# DigitalesSCH.net
KiCad netlist of a schematic drawn in EAGLE
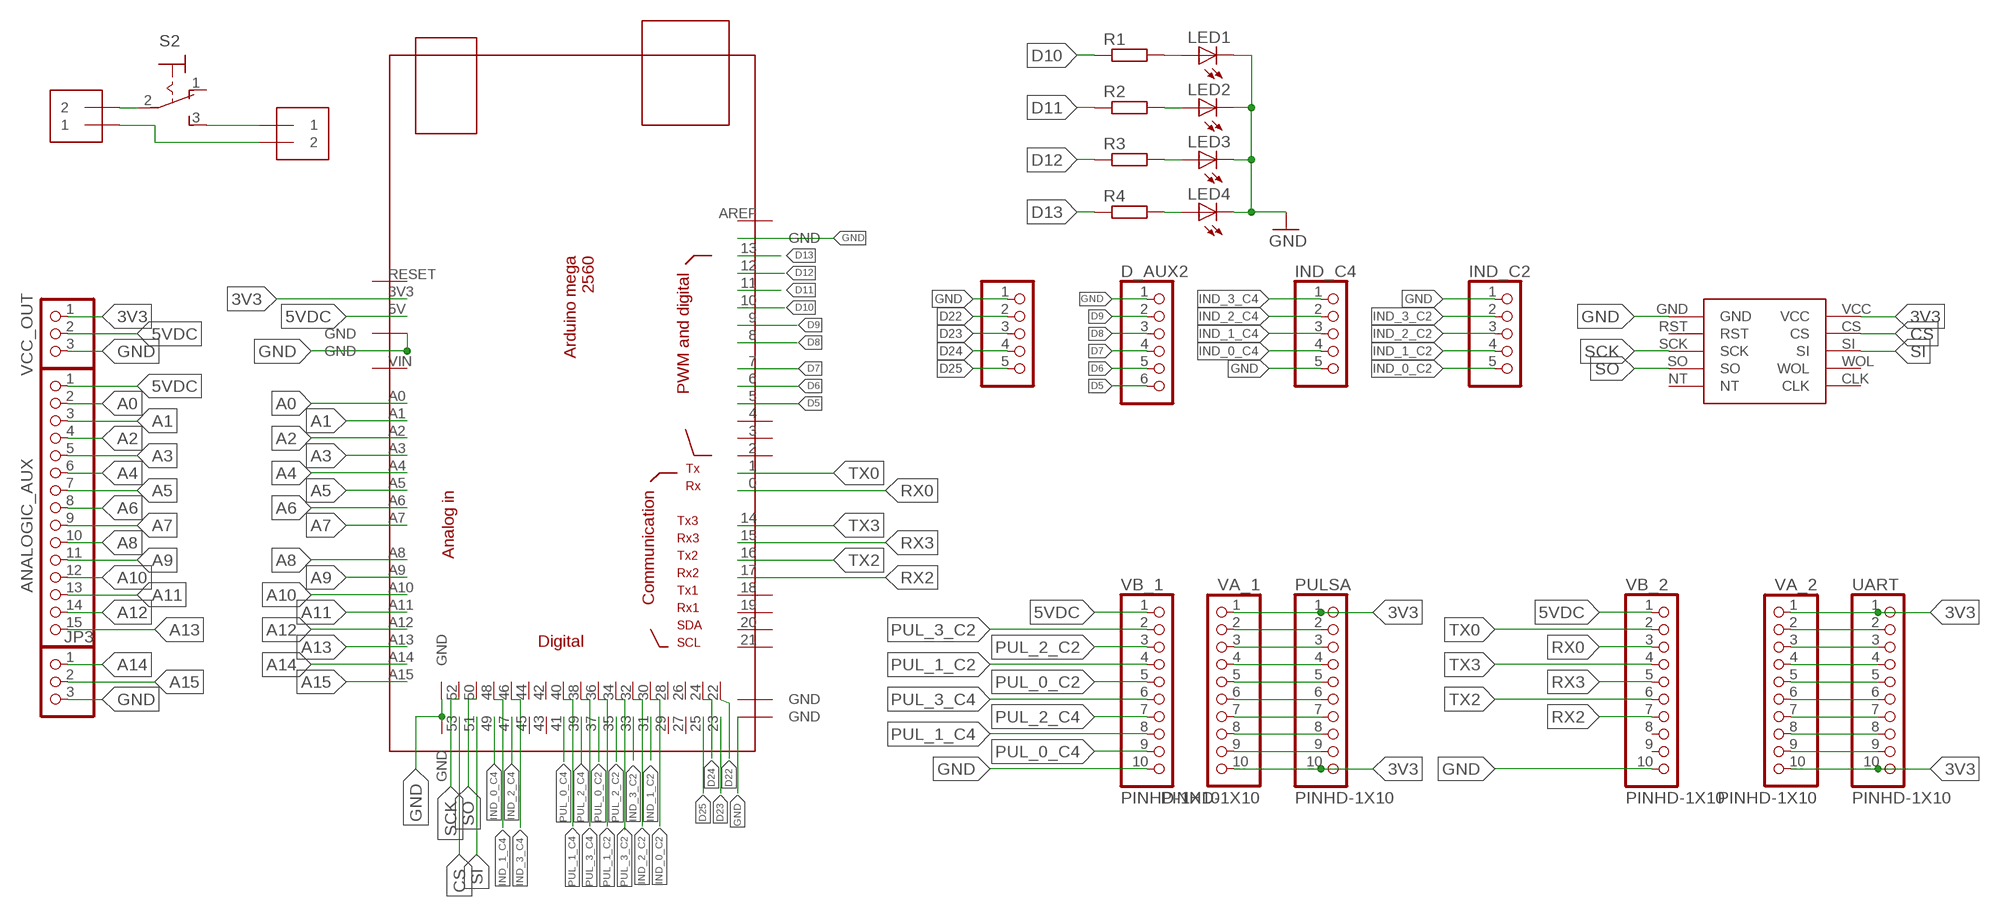
[diagram p0: schematic, sheet 1]

(export (version "E")
  (design (tool "Eeschema 10.0.6"))
  (components
    (comp (ref "ANALOGIC_AUX")
      (value "PINHD-1X15")
      (footprint "eagle-import:1X15")
      (libsource (lib "eagle-import") (part "PINHD-1X15"))
    )
    (comp (ref "D_AUX1")
      (value "PINHD-1X5")
      (footprint "eagle-import:1X05")
      (libsource (lib "eagle-import") (part "PINHD-1X5"))
    )
    (comp (ref "D_AUX2")
      (value "PINHD-1X6")
      (footprint "eagle-import:1X06")
      (libsource (lib "eagle-import") (part "PINHD-1X6"))
    )
    (comp (ref "IND_C2")
      (value "PINHD-1X5")
      (footprint "eagle-import:1X05")
      (libsource (lib "eagle-import") (part "PINHD-1X5"))
    )
    (comp (ref "IND_C4")
      (value "PINHD-1X5")
      (footprint "eagle-import:1X05")
      (libsource (lib "eagle-import") (part "PINHD-1X5"))
    )
    (comp (ref "JP3")
      (value "PINHD-1X3")
      (footprint "eagle-import:1X03")
      (libsource (lib "eagle-import") (part "PINHD-1X3"))
    )
    (comp (ref "LED1")
      (value "LED3MM")
      (footprint "eagle-import:LED3MM")
      (libsource (lib "eagle-import") (part "LED3MM"))
    )
    (comp (ref "LED2")
      (value "LED3MM")
      (footprint "eagle-import:LED3MM")
      (libsource (lib "eagle-import") (part "LED3MM"))
    )
    (comp (ref "LED3")
      (value "LED3MM")
      (footprint "eagle-import:LED3MM")
      (libsource (lib "eagle-import") (part "LED3MM"))
    )
    (comp (ref "LED4")
      (value "LED3MM")
      (footprint "eagle-import:LED3MM")
      (libsource (lib "eagle-import") (part "LED3MM"))
    )
    (comp (ref "PULSA")
      (value "PINHD-1X10")
      (footprint "eagle-import:1X10-BIG")
      (libsource (lib "eagle-import") (part "PINHD-1X10"))
    )
    (comp (ref "R1")
      (value "R-EU_M1206")
      (footprint "eagle-import:M1206")
      (libsource (lib "eagle-import") (part "R-EU_M1206"))
    )
    (comp (ref "R2")
      (value "R-EU_M1206")
      (footprint "eagle-import:M1206")
      (libsource (lib "eagle-import") (part "R-EU_M1206"))
    )
    (comp (ref "R3")
      (value "R-EU_M1206")
      (footprint "eagle-import:M1206")
      (libsource (lib "eagle-import") (part "R-EU_M1206"))
    )
    (comp (ref "R4")
      (value "R-EU_M1206")
      (footprint "eagle-import:M1206")
      (libsource (lib "eagle-import") (part "R-EU_M1206"))
    )
    (comp (ref "S2")
      (value "M9040P")
      (footprint "eagle-import:M9040P")
      (libsource (lib "eagle-import") (part "M9040P"))
    )
    (comp (ref "U$1")
      (value "MEGA_DEVICE")
      (footprint "eagle-import:MEGAOUTLINE")
      (libsource (lib "eagle-import") (part "MEGA_DEVICE"))
    )
    (comp (ref "U$2")
      (value "ENC28J60")
      (footprint "eagle-import:ENC28J60")
      (libsource (lib "eagle-import") (part "ENC28J60"))
    )
    (comp (ref "UART")
      (value "PINHD-1X10")
      (footprint "eagle-import:1X10-BIG")
      (libsource (lib "eagle-import") (part "PINHD-1X10"))
    )
    (comp (ref "VA_1")
      (value "PINHD-1X10")
      (footprint "eagle-import:1X10-BIG")
      (libsource (lib "eagle-import") (part "PINHD-1X10"))
    )
    (comp (ref "VA_2")
      (value "PINHD-1X10")
      (footprint "eagle-import:1X10-BIG")
      (libsource (lib "eagle-import") (part "PINHD-1X10"))
    )
    (comp (ref "VB_1")
      (value "PINHD-1X10")
      (footprint "eagle-import:1X10-BIG")
      (libsource (lib "eagle-import") (part "PINHD-1X10"))
    )
    (comp (ref "VB_2")
      (value "PINHD-1X10")
      (footprint "eagle-import:1X10-BIG")
      (libsource (lib "eagle-import") (part "PINHD-1X10"))
    )
    (comp (ref "VCC_OUT")
      (value "PINHD-1X3")
      (footprint "eagle-import:1X03")
      (libsource (lib "eagle-import") (part "PINHD-1X3"))
    )
    (comp (ref "VIN")
      (value "1X2-3.5MM")
      (footprint "eagle-import:1X2-3.5MM")
      (libsource (lib "eagle-import") (part "1X2-3.5MM"))
    )
    (comp (ref "VOUT")
      (value "1X2-3.5MM")
      (footprint "eagle-import:1X2-3.5MM")
      (libsource (lib "eagle-import") (part "1X2-3.5MM"))
    )
  )
  (nets
    (net (code "1") (name "3V3") (class "Default")
      (node (ref "PULSA") (pin "1") (pinfunction "1_1") (pintype "passive"))
      (node (ref "PULSA") (pin "10") (pinfunction "10_10") (pintype "passive"))
      (node (ref "U$1") (pin "3V3") (pinfunction "3V3_3V3") (pintype "bidirectional"))
      (node (ref "U$2") (pin "VCC") (pinfunction "VCC_VCC") (pintype "bidirectional"))
      (node (ref "UART") (pin "1") (pinfunction "1_1") (pintype "passive"))
      (node (ref "UART") (pin "10") (pinfunction "10_10") (pintype "passive"))
      (node (ref "VA_1") (pin "1") (pinfunction "1_1") (pintype "passive"))
      (node (ref "VA_1") (pin "10") (pinfunction "10_10") (pintype "passive"))
      (node (ref "VA_2") (pin "1") (pinfunction "1_1") (pintype "passive"))
      (node (ref "VA_2") (pin "10") (pinfunction "10_10") (pintype "passive"))
      (node (ref "VCC_OUT") (pin "1") (pinfunction "1_1") (pintype "passive"))
    )
    (net (code "2") (name "5VDC") (class "Default")
      (node (ref "ANALOGIC_AUX") (pin "1") (pinfunction "1_1") (pintype "passive"))
      (node (ref "U$1") (pin "5V") (pinfunction "5V_5V") (pintype "bidirectional"))
      (node (ref "VB_1") (pin "1") (pinfunction "1_1") (pintype "passive"))
      (node (ref "VB_2") (pin "1") (pinfunction "1_1") (pintype "passive"))
      (node (ref "VCC_OUT") (pin "2") (pinfunction "2_2") (pintype "passive"))
    )
    (net (code "3") (name "A0") (class "Default")
      (node (ref "ANALOGIC_AUX") (pin "2") (pinfunction "2_2") (pintype "passive"))
      (node (ref "U$1") (pin "A0") (pinfunction "A0_A0") (pintype "bidirectional"))
    )
    (net (code "4") (name "A1") (class "Default")
      (node (ref "ANALOGIC_AUX") (pin "3") (pinfunction "3_3") (pintype "passive"))
      (node (ref "U$1") (pin "A1") (pinfunction "A1_A1") (pintype "bidirectional"))
    )
    (net (code "5") (name "A2") (class "Default")
      (node (ref "ANALOGIC_AUX") (pin "4") (pinfunction "4_4") (pintype "passive"))
      (node (ref "U$1") (pin "A2") (pinfunction "A2_A2") (pintype "bidirectional"))
    )
    (net (code "6") (name "A3") (class "Default")
      (node (ref "ANALOGIC_AUX") (pin "5") (pinfunction "5_5") (pintype "passive"))
      (node (ref "U$1") (pin "A3") (pinfunction "A3_A3") (pintype "bidirectional"))
    )
    (net (code "7") (name "A4") (class "Default")
      (node (ref "ANALOGIC_AUX") (pin "6") (pinfunction "6_6") (pintype "passive"))
      (node (ref "U$1") (pin "A4") (pinfunction "A4_A4") (pintype "bidirectional"))
    )
    (net (code "8") (name "A5") (class "Default")
      (node (ref "ANALOGIC_AUX") (pin "7") (pinfunction "7_7") (pintype "passive"))
      (node (ref "U$1") (pin "A5") (pinfunction "A5_A5") (pintype "bidirectional"))
    )
    (net (code "9") (name "A6") (class "Default")
      (node (ref "ANALOGIC_AUX") (pin "8") (pinfunction "8_8") (pintype "passive"))
      (node (ref "U$1") (pin "A6") (pinfunction "A6_A6") (pintype "bidirectional"))
    )
    (net (code "10") (name "A7") (class "Default")
      (node (ref "ANALOGIC_AUX") (pin "9") (pinfunction "9_9") (pintype "passive"))
      (node (ref "U$1") (pin "A7") (pinfunction "A7_A7") (pintype "bidirectional"))
    )
    (net (code "11") (name "A8") (class "Default")
      (node (ref "ANALOGIC_AUX") (pin "10") (pinfunction "10_10") (pintype "passive"))
      (node (ref "U$1") (pin "A8") (pinfunction "A8_A8") (pintype "bidirectional"))
    )
    (net (code "12") (name "A9") (class "Default")
      (node (ref "ANALOGIC_AUX") (pin "11") (pinfunction "11_11") (pintype "passive"))
      (node (ref "U$1") (pin "A9") (pinfunction "A9_A9") (pintype "bidirectional"))
    )
    (net (code "13") (name "A10") (class "Default")
      (node (ref "ANALOGIC_AUX") (pin "12") (pinfunction "12_12") (pintype "passive"))
      (node (ref "U$1") (pin "A10") (pinfunction "A10_A10") (pintype "bidirectional"))
    )
    (net (code "14") (name "A11") (class "Default")
      (node (ref "ANALOGIC_AUX") (pin "13") (pinfunction "13_13") (pintype "passive"))
      (node (ref "U$1") (pin "A11") (pinfunction "A11_A11") (pintype "bidirectional"))
    )
    (net (code "15") (name "A12") (class "Default")
      (node (ref "ANALOGIC_AUX") (pin "14") (pinfunction "14_14") (pintype "passive"))
      (node (ref "U$1") (pin "A12") (pinfunction "A12_A12") (pintype "bidirectional"))
    )
    (net (code "16") (name "A13") (class "Default")
      (node (ref "ANALOGIC_AUX") (pin "15") (pinfunction "15_15") (pintype "passive"))
      (node (ref "U$1") (pin "A13") (pinfunction "A13_A13") (pintype "bidirectional"))
    )
    (net (code "17") (name "A14") (class "Default")
      (node (ref "JP3") (pin "1") (pinfunction "1_1") (pintype "passive"))
      (node (ref "U$1") (pin "A14") (pinfunction "A14_A14") (pintype "bidirectional"))
    )
    (net (code "18") (name "A15") (class "Default")
      (node (ref "JP3") (pin "2") (pinfunction "2_2") (pintype "passive"))
      (node (ref "U$1") (pin "A15") (pinfunction "A15_A15") (pintype "bidirectional"))
    )
    (net (code "19") (name "CS") (class "Default")
      (node (ref "U$1") (pin "53") (pinfunction "53_53") (pintype "bidirectional"))
      (node (ref "U$2") (pin "CS") (pinfunction "CS_CS") (pintype "bidirectional"))
    )
    (net (code "20") (name "D5") (class "Default")
      (node (ref "D_AUX2") (pin "6") (pinfunction "6_6") (pintype "passive"))
      (node (ref "U$1") (pin "5") (pinfunction "5_5") (pintype "bidirectional"))
    )
    (net (code "21") (name "D6") (class "Default")
      (node (ref "D_AUX2") (pin "5") (pinfunction "5_5") (pintype "passive"))
      (node (ref "U$1") (pin "6") (pinfunction "6_6") (pintype "bidirectional"))
    )
    (net (code "22") (name "D7") (class "Default")
      (node (ref "D_AUX2") (pin "4") (pinfunction "4_4") (pintype "passive"))
      (node (ref "U$1") (pin "7") (pinfunction "7_7") (pintype "bidirectional"))
    )
    (net (code "23") (name "D8") (class "Default")
      (node (ref "D_AUX2") (pin "3") (pinfunction "3_3") (pintype "passive"))
      (node (ref "U$1") (pin "8") (pinfunction "8_8") (pintype "bidirectional"))
    )
    (net (code "24") (name "D9") (class "Default")
      (node (ref "D_AUX2") (pin "2") (pinfunction "2_2") (pintype "passive"))
      (node (ref "U$1") (pin "9") (pinfunction "9_9") (pintype "bidirectional"))
    )
    (net (code "25") (name "D10") (class "Default")
      (node (ref "R1") (pin "1") (pinfunction "1_1") (pintype "passive"))
      (node (ref "U$1") (pin "10") (pinfunction "10_10") (pintype "bidirectional"))
    )
    (net (code "26") (name "D11") (class "Default")
      (node (ref "R2") (pin "1") (pinfunction "1_1") (pintype "passive"))
      (node (ref "U$1") (pin "11") (pinfunction "11_11") (pintype "bidirectional"))
    )
    (net (code "27") (name "D12") (class "Default")
      (node (ref "R3") (pin "1") (pinfunction "1_1") (pintype "passive"))
      (node (ref "U$1") (pin "12") (pinfunction "12_12") (pintype "bidirectional"))
    )
    (net (code "28") (name "D13") (class "Default")
      (node (ref "R4") (pin "1") (pinfunction "1_1") (pintype "passive"))
      (node (ref "U$1") (pin "13") (pinfunction "13_13") (pintype "bidirectional"))
    )
    (net (code "29") (name "D22") (class "Default")
      (node (ref "D_AUX1") (pin "2") (pinfunction "2_2") (pintype "passive"))
      (node (ref "U$1") (pin "22") (pinfunction "22_22") (pintype "bidirectional"))
    )
    (net (code "30") (name "D23") (class "Default")
      (node (ref "D_AUX1") (pin "3") (pinfunction "3_3") (pintype "passive"))
      (node (ref "U$1") (pin "23") (pinfunction "23_23") (pintype "bidirectional"))
    )
    (net (code "31") (name "D24") (class "Default")
      (node (ref "D_AUX1") (pin "4") (pinfunction "4_4") (pintype "passive"))
      (node (ref "U$1") (pin "24") (pinfunction "24_24") (pintype "bidirectional"))
    )
    (net (code "32") (name "D25") (class "Default")
      (node (ref "D_AUX1") (pin "5") (pinfunction "5_5") (pintype "passive"))
      (node (ref "U$1") (pin "25") (pinfunction "25_25") (pintype "bidirectional"))
    )
    (net (code "33") (name "GND") (class "Default")
      (node (ref "D_AUX1") (pin "1") (pinfunction "1_1") (pintype "passive"))
      (node (ref "D_AUX2") (pin "1") (pinfunction "1_1") (pintype "passive"))
      (node (ref "IND_C2") (pin "1") (pinfunction "1_1") (pintype "passive"))
      (node (ref "IND_C4") (pin "5") (pinfunction "5_5") (pintype "passive"))
      (node (ref "JP3") (pin "3") (pinfunction "3_3") (pintype "passive"))
      (node (ref "LED1") (pin "K") (pinfunction "C_K") (pintype "passive"))
      (node (ref "LED2") (pin "K") (pinfunction "C_K") (pintype "passive"))
      (node (ref "LED3") (pin "K") (pinfunction "C_K") (pintype "passive"))
      (node (ref "LED4") (pin "K") (pinfunction "C_K") (pintype "passive"))
      (node (ref "U$1") (pin "GND@1") (pinfunction "GND_GND@1") (pintype "bidirectional"))
      (node (ref "U$1") (pin "GND@2") (pinfunction "GND_GND@2") (pintype "bidirectional"))
      (node (ref "U$1") (pin "GND@3") (pinfunction "GND_GND@3") (pintype "bidirectional"))
      (node (ref "U$1") (pin "GND@5") (pinfunction "GND_GND@5") (pintype "bidirectional"))
      (node (ref "U$1") (pin "GND@6") (pinfunction "GND_GND@6") (pintype "bidirectional"))
      (node (ref "U$1") (pin "GND@7") (pinfunction "GND_GND@7") (pintype "bidirectional"))
      (node (ref "U$2") (pin "GND") (pinfunction "GND_GND") (pintype "bidirectional"))
      (node (ref "VB_1") (pin "10") (pinfunction "10_10") (pintype "passive"))
      (node (ref "VB_2") (pin "10") (pinfunction "10_10") (pintype "passive"))
      (node (ref "VCC_OUT") (pin "3") (pinfunction "3_3") (pintype "passive"))
    )
    (net (code "34") (name "IND_0_C2") (class "Default")
      (node (ref "IND_C2") (pin "5") (pinfunction "5_5") (pintype "passive"))
      (node (ref "U$1") (pin "30") (pinfunction "30_30") (pintype "bidirectional"))
    )
    (net (code "35") (name "IND_0_C4") (class "Default")
      (node (ref "IND_C4") (pin "4") (pinfunction "4_4") (pintype "passive"))
      (node (ref "U$1") (pin "49") (pinfunction "49_49") (pintype "bidirectional"))
    )
    (net (code "36") (name "IND_1_C2") (class "Default")
      (node (ref "IND_C2") (pin "4") (pinfunction "4_4") (pintype "passive"))
      (node (ref "U$1") (pin "31") (pinfunction "31_31") (pintype "bidirectional"))
    )
    (net (code "37") (name "IND_1_C4") (class "Default")
      (node (ref "IND_C4") (pin "3") (pinfunction "3_3") (pintype "passive"))
      (node (ref "U$1") (pin "48") (pinfunction "48_48") (pintype "bidirectional"))
    )
    (net (code "38") (name "IND_2_C2") (class "Default")
      (node (ref "IND_C2") (pin "3") (pinfunction "3_3") (pintype "passive"))
      (node (ref "U$1") (pin "32") (pinfunction "32_32") (pintype "bidirectional"))
    )
    (net (code "39") (name "IND_2_C4") (class "Default")
      (node (ref "IND_C4") (pin "2") (pinfunction "2_2") (pintype "passive"))
      (node (ref "U$1") (pin "47") (pinfunction "47_47") (pintype "bidirectional"))
    )
    (net (code "40") (name "IND_3_C2") (class "Default")
      (node (ref "IND_C2") (pin "2") (pinfunction "2_2") (pintype "passive"))
      (node (ref "U$1") (pin "33") (pinfunction "33_33") (pintype "bidirectional"))
    )
    (net (code "41") (name "IND_3_C4") (class "Default")
      (node (ref "IND_C4") (pin "1") (pinfunction "1_1") (pintype "passive"))
      (node (ref "U$1") (pin "46") (pinfunction "46_46") (pintype "bidirectional"))
    )
    (net (code "42") (name "Net-(LED1-PadA)") (class "Default")
      (node (ref "LED1") (pin "A") (pinfunction "A_A") (pintype "passive"))
      (node (ref "R1") (pin "2") (pinfunction "2_2") (pintype "passive"))
    )
    (net (code "43") (name "Net-(LED2-PadA)") (class "Default")
      (node (ref "LED2") (pin "A") (pinfunction "A_A") (pintype "passive"))
      (node (ref "R2") (pin "2") (pinfunction "2_2") (pintype "passive"))
    )
    (net (code "44") (name "Net-(LED3-PadA)") (class "Default")
      (node (ref "LED3") (pin "A") (pinfunction "A_A") (pintype "passive"))
      (node (ref "R3") (pin "2") (pinfunction "2_2") (pintype "passive"))
    )
    (net (code "45") (name "Net-(LED4-PadA)") (class "Default")
      (node (ref "LED4") (pin "A") (pinfunction "A_A") (pintype "passive"))
      (node (ref "R4") (pin "2") (pinfunction "2_2") (pintype "passive"))
    )
    (net (code "46") (name "Net-(PULSA-Pad2)") (class "Default")
      (node (ref "PULSA") (pin "2") (pinfunction "2_2") (pintype "passive"))
      (node (ref "VA_1") (pin "2") (pinfunction "2_2") (pintype "passive"))
    )
    (net (code "47") (name "Net-(PULSA-Pad3)") (class "Default")
      (node (ref "PULSA") (pin "3") (pinfunction "3_3") (pintype "passive"))
      (node (ref "VA_1") (pin "3") (pinfunction "3_3") (pintype "passive"))
    )
    (net (code "48") (name "Net-(PULSA-Pad4)") (class "Default")
      (node (ref "PULSA") (pin "4") (pinfunction "4_4") (pintype "passive"))
      (node (ref "VA_1") (pin "4") (pinfunction "4_4") (pintype "passive"))
    )
    (net (code "49") (name "Net-(PULSA-Pad5)") (class "Default")
      (node (ref "PULSA") (pin "5") (pinfunction "5_5") (pintype "passive"))
      (node (ref "VA_1") (pin "5") (pinfunction "5_5") (pintype "passive"))
    )
    (net (code "50") (name "Net-(PULSA-Pad6)") (class "Default")
      (node (ref "PULSA") (pin "6") (pinfunction "6_6") (pintype "passive"))
      (node (ref "VA_1") (pin "6") (pinfunction "6_6") (pintype "passive"))
    )
    (net (code "51") (name "Net-(PULSA-Pad7)") (class "Default")
      (node (ref "PULSA") (pin "7") (pinfunction "7_7") (pintype "passive"))
      (node (ref "VA_1") (pin "7") (pinfunction "7_7") (pintype "passive"))
    )
    (net (code "52") (name "Net-(PULSA-Pad8)") (class "Default")
      (node (ref "PULSA") (pin "8") (pinfunction "8_8") (pintype "passive"))
      (node (ref "VA_1") (pin "8") (pinfunction "8_8") (pintype "passive"))
    )
    (net (code "53") (name "Net-(PULSA-Pad9)") (class "Default")
      (node (ref "PULSA") (pin "9") (pinfunction "9_9") (pintype "passive"))
      (node (ref "VA_1") (pin "9") (pinfunction "9_9") (pintype "passive"))
    )
    (net (code "54") (name "Net-(S2-P)") (class "Default")
      (node (ref "S2") (pin "2") (pinfunction "P_2") (pintype "passive"))
      (node (ref "VIN") (pin "2") (pinfunction "2_2") (pintype "passive"))
    )
    (net (code "55") (name "Net-(S2-S)") (class "Default")
      (node (ref "S2") (pin "3") (pinfunction "S_3") (pintype "passive"))
      (node (ref "VOUT") (pin "1") (pinfunction "1_1") (pintype "passive"))
    )
    (net (code "56") (name "Net-(UART-Pad2)") (class "Default")
      (node (ref "UART") (pin "2") (pinfunction "2_2") (pintype "passive"))
      (node (ref "VA_2") (pin "2") (pinfunction "2_2") (pintype "passive"))
    )
    (net (code "57") (name "Net-(UART-Pad3)") (class "Default")
      (node (ref "UART") (pin "3") (pinfunction "3_3") (pintype "passive"))
      (node (ref "VA_2") (pin "3") (pinfunction "3_3") (pintype "passive"))
    )
    (net (code "58") (name "Net-(UART-Pad4)") (class "Default")
      (node (ref "UART") (pin "4") (pinfunction "4_4") (pintype "passive"))
      (node (ref "VA_2") (pin "4") (pinfunction "4_4") (pintype "passive"))
    )
    (net (code "59") (name "Net-(UART-Pad5)") (class "Default")
      (node (ref "UART") (pin "5") (pinfunction "5_5") (pintype "passive"))
      (node (ref "VA_2") (pin "5") (pinfunction "5_5") (pintype "passive"))
    )
    (net (code "60") (name "Net-(UART-Pad6)") (class "Default")
      (node (ref "UART") (pin "6") (pinfunction "6_6") (pintype "passive"))
      (node (ref "VA_2") (pin "6") (pinfunction "6_6") (pintype "passive"))
    )
    (net (code "61") (name "Net-(UART-Pad7)") (class "Default")
      (node (ref "UART") (pin "7") (pinfunction "7_7") (pintype "passive"))
      (node (ref "VA_2") (pin "7") (pinfunction "7_7") (pintype "passive"))
    )
    (net (code "62") (name "Net-(UART-Pad8)") (class "Default")
      (node (ref "UART") (pin "8") (pinfunction "8_8") (pintype "passive"))
      (node (ref "VA_2") (pin "8") (pinfunction "8_8") (pintype "passive"))
    )
    (net (code "63") (name "Net-(UART-Pad9)") (class "Default")
      (node (ref "UART") (pin "9") (pinfunction "9_9") (pintype "passive"))
      (node (ref "VA_2") (pin "9") (pinfunction "9_9") (pintype "passive"))
    )
    (net (code "64") (name "Net-(VIN-Pad1)") (class "Default")
      (node (ref "VIN") (pin "1") (pinfunction "1_1") (pintype "passive"))
      (node (ref "VOUT") (pin "2") (pinfunction "2_2") (pintype "passive"))
    )
    (net (code "65") (name "PUL_0_C2") (class "Default")
      (node (ref "U$1") (pin "37") (pinfunction "37_37") (pintype "bidirectional"))
      (node (ref "VB_1") (pin "5") (pinfunction "5_5") (pintype "passive"))
    )
    (net (code "66") (name "PUL_0_C4") (class "Default")
      (node (ref "U$1") (pin "41") (pinfunction "41_41") (pintype "bidirectional"))
      (node (ref "VB_1") (pin "9") (pinfunction "9_9") (pintype "passive"))
    )
    (net (code "67") (name "PUL_1_C2") (class "Default")
      (node (ref "U$1") (pin "36") (pinfunction "36_36") (pintype "bidirectional"))
      (node (ref "VB_1") (pin "4") (pinfunction "4_4") (pintype "passive"))
    )
    (net (code "68") (name "PUL_1_C4") (class "Default")
      (node (ref "U$1") (pin "40") (pinfunction "40_40") (pintype "bidirectional"))
      (node (ref "VB_1") (pin "8") (pinfunction "8_8") (pintype "passive"))
    )
    (net (code "69") (name "PUL_2_C2") (class "Default")
      (node (ref "U$1") (pin "35") (pinfunction "35_35") (pintype "bidirectional"))
      (node (ref "VB_1") (pin "3") (pinfunction "3_3") (pintype "passive"))
    )
    (net (code "70") (name "PUL_2_C4") (class "Default")
      (node (ref "U$1") (pin "39") (pinfunction "39_39") (pintype "bidirectional"))
      (node (ref "VB_1") (pin "7") (pinfunction "7_7") (pintype "passive"))
    )
    (net (code "71") (name "PUL_3_C2") (class "Default")
      (node (ref "U$1") (pin "34") (pinfunction "34_34") (pintype "bidirectional"))
      (node (ref "VB_1") (pin "2") (pinfunction "2_2") (pintype "passive"))
    )
    (net (code "72") (name "PUL_3_C4") (class "Default")
      (node (ref "U$1") (pin "38") (pinfunction "38_38") (pintype "bidirectional"))
      (node (ref "VB_1") (pin "6") (pinfunction "6_6") (pintype "passive"))
    )
    (net (code "73") (name "RX0") (class "Default")
      (node (ref "U$1") (pin "0") (pinfunction "0_0") (pintype "bidirectional"))
      (node (ref "VB_2") (pin "3") (pinfunction "3_3") (pintype "passive"))
    )
    (net (code "74") (name "RX2") (class "Default")
      (node (ref "U$1") (pin "17") (pinfunction "17_17") (pintype "bidirectional"))
      (node (ref "VB_2") (pin "7") (pinfunction "7_7") (pintype "passive"))
    )
    (net (code "75") (name "RX3") (class "Default")
      (node (ref "U$1") (pin "15") (pinfunction "15_15") (pintype "bidirectional"))
      (node (ref "VB_2") (pin "5") (pinfunction "5_5") (pintype "passive"))
    )
    (net (code "76") (name "SCK") (class "Default")
      (node (ref "U$1") (pin "52") (pinfunction "52_52") (pintype "bidirectional"))
      (node (ref "U$2") (pin "SCK") (pinfunction "SCK_SCK") (pintype "bidirectional"))
    )
    (net (code "77") (name "SI") (class "Default")
      (node (ref "U$1") (pin "51") (pinfunction "51_51") (pintype "bidirectional"))
      (node (ref "U$2") (pin "SI") (pinfunction "SI_SI") (pintype "bidirectional"))
    )
    (net (code "78") (name "SO") (class "Default")
      (node (ref "U$1") (pin "50") (pinfunction "50_50") (pintype "bidirectional"))
      (node (ref "U$2") (pin "SO") (pinfunction "SO_SO") (pintype "bidirectional"))
    )
    (net (code "79") (name "TX0") (class "Default")
      (node (ref "U$1") (pin "1") (pinfunction "1_1") (pintype "bidirectional"))
      (node (ref "VB_2") (pin "2") (pinfunction "2_2") (pintype "passive"))
    )
    (net (code "80") (name "TX2") (class "Default")
      (node (ref "U$1") (pin "16") (pinfunction "16_16") (pintype "bidirectional"))
      (node (ref "VB_2") (pin "6") (pinfunction "6_6") (pintype "passive"))
    )
    (net (code "81") (name "TX3") (class "Default")
      (node (ref "U$1") (pin "14") (pinfunction "14_14") (pintype "bidirectional"))
      (node (ref "VB_2") (pin "4") (pinfunction "4_4") (pintype "passive"))
    )
    (net (code "82") (name "unconnected-(S2-O-Pad1)") (class "Default")
      (node (ref "S2") (pin "1") (pinfunction "O_1") (pintype "passive"))
    )
    (net (code "83") (name "unconnected-(U$1-GND-PadGND@4)") (class "Default")
      (node (ref "U$1") (pin "GND@4") (pinfunction "GND_GND@4") (pintype "bidirectional"))
    )
    (net (code "84") (name "unconnected-(U$1-Pad2)") (class "Default")
      (node (ref "U$1") (pin "2") (pinfunction "2_2") (pintype "bidirectional"))
    )
    (net (code "85") (name "unconnected-(U$1-Pad3)") (class "Default")
      (node (ref "U$1") (pin "3") (pinfunction "3_3") (pintype "bidirectional"))
    )
    (net (code "86") (name "unconnected-(U$1-Pad4)") (class "Default")
      (node (ref "U$1") (pin "4") (pinfunction "4_4") (pintype "bidirectional"))
    )
    (net (code "87") (name "unconnected-(U$1-Pad18)") (class "Default")
      (node (ref "U$1") (pin "18") (pinfunction "18_18") (pintype "bidirectional"))
    )
    (net (code "88") (name "unconnected-(U$1-Pad19)") (class "Default")
      (node (ref "U$1") (pin "19") (pinfunction "19_19") (pintype "bidirectional"))
    )
    (net (code "89") (name "unconnected-(U$1-Pad20)") (class "Default")
      (node (ref "U$1") (pin "20") (pinfunction "20_20") (pintype "bidirectional"))
    )
    (net (code "90") (name "unconnected-(U$1-Pad21)") (class "Default")
      (node (ref "U$1") (pin "21") (pinfunction "21_21") (pintype "bidirectional"))
    )
    (net (code "91") (name "unconnected-(U$1-Pad26)") (class "Default")
      (node (ref "U$1") (pin "26") (pinfunction "26_26") (pintype "bidirectional"))
    )
    (net (code "92") (name "unconnected-(U$1-Pad27)") (class "Default")
      (node (ref "U$1") (pin "27") (pinfunction "27_27") (pintype "bidirectional"))
    )
    (net (code "93") (name "unconnected-(U$1-Pad28)") (class "Default")
      (node (ref "U$1") (pin "28") (pinfunction "28_28") (pintype "bidirectional"))
    )
    (net (code "94") (name "unconnected-(U$1-Pad29)") (class "Default")
      (node (ref "U$1") (pin "29") (pinfunction "29_29") (pintype "bidirectional"))
    )
    (net (code "95") (name "unconnected-(U$1-Pad42)") (class "Default")
      (node (ref "U$1") (pin "42") (pinfunction "42_42") (pintype "bidirectional"))
    )
    (net (code "96") (name "unconnected-(U$1-Pad43)") (class "Default")
      (node (ref "U$1") (pin "43") (pinfunction "43_43") (pintype "bidirectional"))
    )
    (net (code "97") (name "unconnected-(U$1-Pad44)") (class "Default")
      (node (ref "U$1") (pin "44") (pinfunction "44_44") (pintype "bidirectional"))
    )
    (net (code "98") (name "unconnected-(U$1-Pad45)") (class "Default")
      (node (ref "U$1") (pin "45") (pinfunction "45_45") (pintype "bidirectional"))
    )
    (net (code "99") (name "unconnected-(U$1-PadAREF)") (class "Default")
      (node (ref "U$1") (pin "AREF") (pinfunction "AREF_AREF") (pintype "bidirectional"))
    )
    (net (code "100") (name "unconnected-(U$1-PadRESET)") (class "Default")
      (node (ref "U$1") (pin "RESET") (pinfunction "RESET_RESET") (pintype "bidirectional"))
    )
    (net (code "101") (name "unconnected-(U$1-PadVIN)") (class "Default")
      (node (ref "U$1") (pin "VIN") (pinfunction "VIN_VIN") (pintype "bidirectional"))
    )
    (net (code "102") (name "unconnected-(U$2-PadCLK)") (class "Default")
      (node (ref "U$2") (pin "CLK") (pinfunction "CLK_CLK") (pintype "bidirectional"))
    )
    (net (code "103") (name "unconnected-(U$2-PadNT)") (class "Default")
      (node (ref "U$2") (pin "NT") (pinfunction "NT_NT") (pintype "bidirectional"))
    )
    (net (code "104") (name "unconnected-(U$2-PadRST)") (class "Default")
      (node (ref "U$2") (pin "RST") (pinfunction "RST_RST") (pintype "bidirectional"))
    )
    (net (code "105") (name "unconnected-(U$2-PadWOL)") (class "Default")
      (node (ref "U$2") (pin "WOL") (pinfunction "WOL_WOL") (pintype "bidirectional"))
    )
    (net (code "106") (name "unconnected-(VB_2-Pad8)") (class "Default")
      (node (ref "VB_2") (pin "8") (pinfunction "8_8") (pintype "passive"))
    )
    (net (code "107") (name "unconnected-(VB_2-Pad9)") (class "Default")
      (node (ref "VB_2") (pin "9") (pinfunction "9_9") (pintype "passive"))
    )
  )
)
